# 13_FLOW_Sensor.net
KiCad netlist of a schematic drawn in Altium Designer
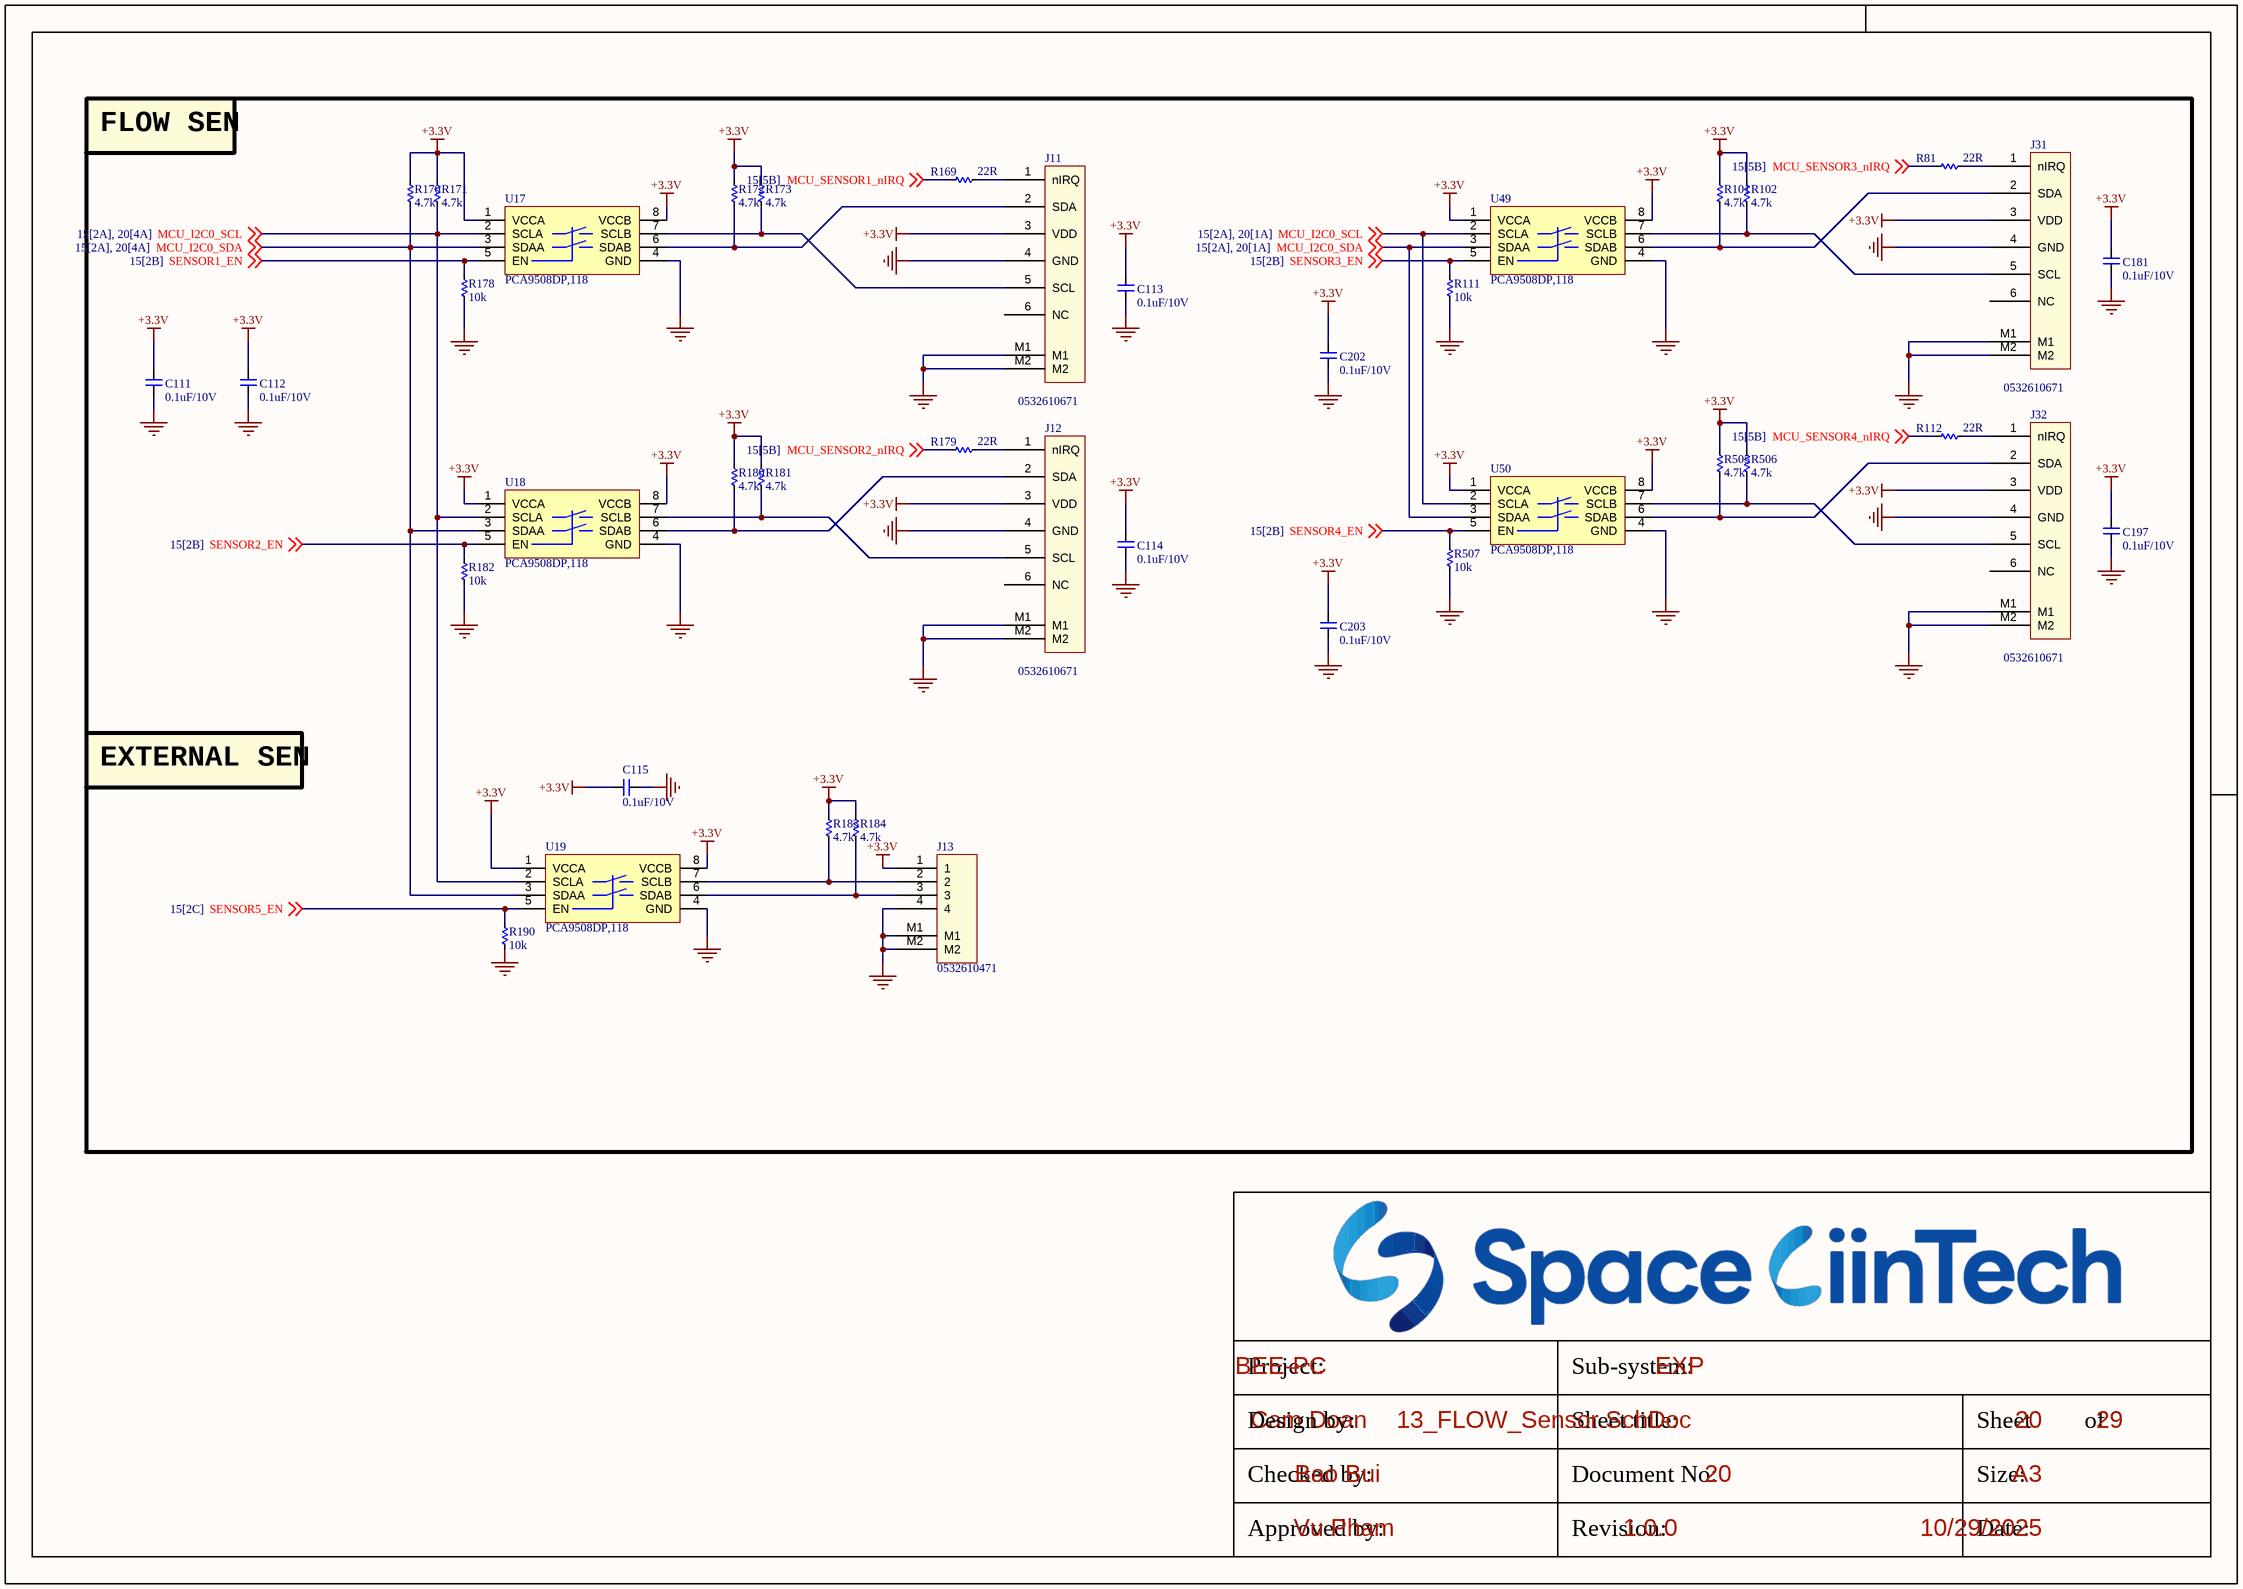
[diagram p0: 13_FLOW_Sensor.SchDoc]

(export (version "E")
  (design (tool "Eeschema 10.0.6"))
  (components
    (comp (ref "C111")
      (value "0.1uF/10V")
      (footprint "CAP_C_1005X60")
      (description "CAP CHIP")
      (libsource (lib "LABLIB") (part "_CAP_C_2"))
    )
    (comp (ref "C112")
      (value "0.1uF/10V")
      (footprint "CAP_C_1005X60")
      (description "CAP CHIP")
      (libsource (lib "LABLIB") (part "_CAP_C_2"))
    )
    (comp (ref "C113")
      (value "0.1uF/10V")
      (footprint "CAP_C_1005X60")
      (description "CAP CHIP")
      (libsource (lib "LABLIB") (part "_CAP_C_2"))
    )
    (comp (ref "C114")
      (value "0.1uF/10V")
      (footprint "CAP_C_1005X60")
      (description "CAP CHIP")
      (libsource (lib "LABLIB") (part "_CAP_C_2"))
    )
    (comp (ref "C115")
      (value "0.1uF/10V")
      (footprint "CAP_C_1005X60")
      (description "CAP CHIP")
      (libsource (lib "LABLIB") (part "_CAP_C_2"))
    )
    (comp (ref "C181")
      (value "0.1uF/10V")
      (footprint "CAP_C_1005X60")
      (description "CAP CHIP")
      (libsource (lib "LABLIB") (part "_CAP_C_2"))
    )
    (comp (ref "C197")
      (value "0.1uF/10V")
      (footprint "CAP_C_1005X60")
      (description "CAP CHIP")
      (libsource (lib "LABLIB") (part "_CAP_C_2"))
    )
    (comp (ref "C202")
      (value "0.1uF/10V")
      (footprint "CAP_C_1005X60")
      (description "CAP CHIP")
      (libsource (lib "LABLIB") (part "_CAP_C_2"))
    )
    (comp (ref "C203")
      (value "0.1uF/10V")
      (footprint "CAP_C_1005X60")
      (description "CAP CHIP")
      (libsource (lib "LABLIB") (part "_CAP_C_2"))
    )
    (comp (ref "J11")
      (value "0532610671")
      (footprint "MOLEX_0532610671")
      (libsource (lib "new_component") (part "FLOW_SENSOR"))
    )
    (comp (ref "J12")
      (value "0532610671")
      (footprint "MOLEX_0532610671")
      (libsource (lib "new_component") (part "FLOW_SENSOR"))
    )
    (comp (ref "J13")
      (value "0532610471")
      (footprint "MOLEX_0532610471")
      (libsource (lib "LABLIB") (part "Header 4x1_2M"))
    )
    (comp (ref "J31")
      (value "0532610671")
      (footprint "MOLEX_0532610671")
      (libsource (lib "new_component") (part "FLOW_SENSOR"))
    )
    (comp (ref "J32")
      (value "0532610671")
      (footprint "MOLEX_0532610671")
      (libsource (lib "new_component") (part "FLOW_SENSOR"))
    )
    (comp (ref "R81")
      (value "22R")
      (footprint "RES_C_1005X40")
      (description "RES")
      (libsource (lib "LABLIB") (part "_RES_B_2"))
    )
    (comp (ref "R101")
      (value "4.7k")
      (footprint "RES_C_1005X40")
      (description "RES")
      (libsource (lib "LABLIB") (part "_RES_B_2"))
    )
    (comp (ref "R102")
      (value "4.7k")
      (footprint "RES_C_1005X40")
      (description "RES")
      (libsource (lib "LABLIB") (part "_RES_B_2"))
    )
    (comp (ref "R111")
      (value "10k")
      (footprint "RES_C_1005X40")
      (description "RES")
      (libsource (lib "LABLIB") (part "_RES_B_2"))
    )
    (comp (ref "R112")
      (value "22R")
      (footprint "RES_C_1005X40")
      (description "RES")
      (libsource (lib "LABLIB") (part "_RES_B_2"))
    )
    (comp (ref "R169")
      (value "22R")
      (footprint "RES_C_1005X40")
      (description "RES")
      (libsource (lib "LABLIB") (part "_RES_B_2"))
    )
    (comp (ref "R170")
      (value "4.7k")
      (footprint "RES_C_1005X40")
      (description "RES")
      (libsource (lib "LABLIB") (part "_RES_B_2"))
    )
    (comp (ref "R171")
      (value "4.7k")
      (footprint "RES_C_1005X40")
      (description "RES")
      (libsource (lib "LABLIB") (part "_RES_B_2"))
    )
    (comp (ref "R172")
      (value "4.7k")
      (footprint "RES_C_1005X40")
      (description "RES")
      (libsource (lib "LABLIB") (part "_RES_B_2"))
    )
    (comp (ref "R173")
      (value "4.7k")
      (footprint "RES_C_1005X40")
      (description "RES")
      (libsource (lib "LABLIB") (part "_RES_B_2"))
    )
    (comp (ref "R178")
      (value "10k")
      (footprint "RES_C_1005X40")
      (description "RES")
      (libsource (lib "LABLIB") (part "_RES_B_2"))
    )
    (comp (ref "R179")
      (value "22R")
      (footprint "RES_C_1005X40")
      (description "RES")
      (libsource (lib "LABLIB") (part "_RES_B_2"))
    )
    (comp (ref "R180")
      (value "4.7k")
      (footprint "RES_C_1005X40")
      (description "RES")
      (libsource (lib "LABLIB") (part "_RES_B_2"))
    )
    (comp (ref "R181")
      (value "4.7k")
      (footprint "RES_C_1005X40")
      (description "RES")
      (libsource (lib "LABLIB") (part "_RES_B_2"))
    )
    (comp (ref "R182")
      (value "10k")
      (footprint "RES_C_1005X40")
      (description "RES")
      (libsource (lib "LABLIB") (part "_RES_B_2"))
    )
    (comp (ref "R183")
      (value "4.7k")
      (footprint "RES_C_1005X40")
      (description "RES")
      (libsource (lib "LABLIB") (part "_RES_B_2"))
    )
    (comp (ref "R184")
      (value "4.7k")
      (footprint "RES_C_1005X40")
      (description "RES")
      (libsource (lib "LABLIB") (part "_RES_B_2"))
    )
    (comp (ref "R190")
      (value "10k")
      (footprint "RES_C_1005X40")
      (description "RES")
      (libsource (lib "LABLIB") (part "_RES_B_2"))
    )
    (comp (ref "R505")
      (value "4.7k")
      (footprint "RES_C_1005X40")
      (description "RES")
      (libsource (lib "LABLIB") (part "_RES_B_2"))
    )
    (comp (ref "R506")
      (value "4.7k")
      (footprint "RES_C_1005X40")
      (description "RES")
      (libsource (lib "LABLIB") (part "_RES_B_2"))
    )
    (comp (ref "R507")
      (value "10k")
      (footprint "RES_C_1005X40")
      (description "RES")
      (libsource (lib "LABLIB") (part "_RES_B_2"))
    )
    (comp (ref "U17")
      (value "PCA9508DP,118")
      (footprint "TSOP8")
      (libsource (lib "EXP_HW_V3") (part "PCA9508DP,118"))
    )
    (comp (ref "U18")
      (value "PCA9508DP,118")
      (footprint "TSOP8")
      (libsource (lib "EXP_HW_V3") (part "PCA9508DP,118"))
    )
    (comp (ref "U19")
      (value "PCA9508DP,118")
      (footprint "TSOP8")
      (libsource (lib "EXP_HW_V3") (part "PCA9508DP,118"))
    )
    (comp (ref "U49")
      (value "PCA9508DP,118")
      (footprint "TSOP8")
      (libsource (lib "EXP_HW_V3") (part "PCA9508DP,118"))
    )
    (comp (ref "U50")
      (value "PCA9508DP,118")
      (footprint "TSOP8")
      (libsource (lib "EXP_HW_V3") (part "PCA9508DP,118"))
    )
  )
  (nets
    (net (code "1") (name "+3.3V") (class "Default")
      (node (ref "C111") (pin "2") (pinfunction "2_2") (pintype "passive"))
      (node (ref "C112") (pin "2") (pinfunction "2_2") (pintype "passive"))
      (node (ref "C113") (pin "2") (pinfunction "2_2") (pintype "passive"))
      (node (ref "C114") (pin "2") (pinfunction "2_2") (pintype "passive"))
      (node (ref "C115") (pin "2") (pinfunction "2_2") (pintype "passive"))
      (node (ref "C181") (pin "2") (pinfunction "2_2") (pintype "passive"))
      (node (ref "C197") (pin "2") (pinfunction "2_2") (pintype "passive"))
      (node (ref "C202") (pin "2") (pinfunction "2_2") (pintype "passive"))
      (node (ref "C203") (pin "2") (pinfunction "2_2") (pintype "passive"))
      (node (ref "J11") (pin "3") (pinfunction "VDD_3") (pintype "passive"))
      (node (ref "J12") (pin "3") (pinfunction "VDD_3") (pintype "passive"))
      (node (ref "J13") (pin "1") (pinfunction "1_1") (pintype "passive"))
      (node (ref "J31") (pin "3") (pinfunction "VDD_3") (pintype "passive"))
      (node (ref "J32") (pin "3") (pinfunction "VDD_3") (pintype "passive"))
      (node (ref "R101") (pin "1") (pinfunction "1_1") (pintype "passive"))
      (node (ref "R102") (pin "1") (pinfunction "1_1") (pintype "passive"))
      (node (ref "R170") (pin "1") (pinfunction "1_1") (pintype "passive"))
      (node (ref "R171") (pin "1") (pinfunction "1_1") (pintype "passive"))
      (node (ref "R172") (pin "1") (pinfunction "1_1") (pintype "passive"))
      (node (ref "R173") (pin "1") (pinfunction "1_1") (pintype "passive"))
      (node (ref "R180") (pin "1") (pinfunction "1_1") (pintype "passive"))
      (node (ref "R181") (pin "1") (pinfunction "1_1") (pintype "passive"))
      (node (ref "R183") (pin "1") (pinfunction "1_1") (pintype "passive"))
      (node (ref "R184") (pin "1") (pinfunction "1_1") (pintype "passive"))
      (node (ref "R505") (pin "1") (pinfunction "1_1") (pintype "passive"))
      (node (ref "R506") (pin "1") (pinfunction "1_1") (pintype "passive"))
      (node (ref "U17") (pin "1") (pinfunction "VCCA_1") (pintype "passive"))
      (node (ref "U17") (pin "8") (pinfunction "VCCB_8") (pintype "passive"))
      (node (ref "U18") (pin "1") (pinfunction "VCCA_1") (pintype "passive"))
      (node (ref "U18") (pin "8") (pinfunction "VCCB_8") (pintype "passive"))
      (node (ref "U19") (pin "1") (pinfunction "VCCA_1") (pintype "passive"))
      (node (ref "U19") (pin "8") (pinfunction "VCCB_8") (pintype "passive"))
      (node (ref "U49") (pin "1") (pinfunction "VCCA_1") (pintype "passive"))
      (node (ref "U49") (pin "8") (pinfunction "VCCB_8") (pintype "passive"))
      (node (ref "U50") (pin "1") (pinfunction "VCCA_1") (pintype "passive"))
      (node (ref "U50") (pin "8") (pinfunction "VCCB_8") (pintype "passive"))
    )
    (net (code "2") (name "GND") (class "Default")
      (node (ref "C111") (pin "1") (pinfunction "1_1") (pintype "passive"))
      (node (ref "C112") (pin "1") (pinfunction "1_1") (pintype "passive"))
      (node (ref "C113") (pin "1") (pinfunction "1_1") (pintype "passive"))
      (node (ref "C114") (pin "1") (pinfunction "1_1") (pintype "passive"))
      (node (ref "C115") (pin "1") (pinfunction "1_1") (pintype "passive"))
      (node (ref "C181") (pin "1") (pinfunction "1_1") (pintype "passive"))
      (node (ref "C197") (pin "1") (pinfunction "1_1") (pintype "passive"))
      (node (ref "C202") (pin "1") (pinfunction "1_1") (pintype "passive"))
      (node (ref "C203") (pin "1") (pinfunction "1_1") (pintype "passive"))
      (node (ref "J11") (pin "4") (pinfunction "GND_4") (pintype "passive"))
      (node (ref "J11") (pin "M1") (pinfunction "M1_M1") (pintype "passive"))
      (node (ref "J11") (pin "M2") (pinfunction "M2_M2") (pintype "passive"))
      (node (ref "J12") (pin "4") (pinfunction "GND_4") (pintype "passive"))
      (node (ref "J12") (pin "M1") (pinfunction "M1_M1") (pintype "passive"))
      (node (ref "J12") (pin "M2") (pinfunction "M2_M2") (pintype "passive"))
      (node (ref "J13") (pin "4") (pinfunction "4_4") (pintype "passive"))
      (node (ref "J13") (pin "M1") (pinfunction "M1_M1") (pintype "passive"))
      (node (ref "J13") (pin "M2") (pinfunction "M2_M2") (pintype "passive"))
      (node (ref "J31") (pin "4") (pinfunction "GND_4") (pintype "passive"))
      (node (ref "J31") (pin "M1") (pinfunction "M1_M1") (pintype "passive"))
      (node (ref "J31") (pin "M2") (pinfunction "M2_M2") (pintype "passive"))
      (node (ref "J32") (pin "4") (pinfunction "GND_4") (pintype "passive"))
      (node (ref "J32") (pin "M1") (pinfunction "M1_M1") (pintype "passive"))
      (node (ref "J32") (pin "M2") (pinfunction "M2_M2") (pintype "passive"))
      (node (ref "R111") (pin "2") (pinfunction "2_2") (pintype "passive"))
      (node (ref "R178") (pin "2") (pinfunction "2_2") (pintype "passive"))
      (node (ref "R182") (pin "2") (pinfunction "2_2") (pintype "passive"))
      (node (ref "R190") (pin "2") (pinfunction "2_2") (pintype "passive"))
      (node (ref "R507") (pin "2") (pinfunction "2_2") (pintype "passive"))
      (node (ref "U17") (pin "4") (pinfunction "GND_4") (pintype "passive"))
      (node (ref "U18") (pin "4") (pinfunction "GND_4") (pintype "passive"))
      (node (ref "U19") (pin "4") (pinfunction "GND_4") (pintype "passive"))
      (node (ref "U49") (pin "4") (pinfunction "GND_4") (pintype "passive"))
      (node (ref "U50") (pin "4") (pinfunction "GND_4") (pintype "passive"))
    )
    (net (code "3") (name "MCU_I2C0_SCL") (class "Default")
      (node (ref "R171") (pin "2") (pinfunction "2_2") (pintype "passive"))
      (node (ref "U17") (pin "2") (pinfunction "SCLA_2") (pintype "passive"))
      (node (ref "U18") (pin "2") (pinfunction "SCLA_2") (pintype "passive"))
      (node (ref "U19") (pin "2") (pinfunction "SCLA_2") (pintype "passive"))
      (node (ref "U49") (pin "2") (pinfunction "SCLA_2") (pintype "passive"))
      (node (ref "U50") (pin "2") (pinfunction "SCLA_2") (pintype "passive"))
    )
    (net (code "4") (name "MCU_I2C0_SDA") (class "Default")
      (node (ref "R170") (pin "2") (pinfunction "2_2") (pintype "passive"))
      (node (ref "U17") (pin "3") (pinfunction "SDAA_3") (pintype "passive"))
      (node (ref "U18") (pin "3") (pinfunction "SDAA_3") (pintype "passive"))
      (node (ref "U19") (pin "3") (pinfunction "SDAA_3") (pintype "passive"))
      (node (ref "U49") (pin "3") (pinfunction "SDAA_3") (pintype "passive"))
      (node (ref "U50") (pin "3") (pinfunction "SDAA_3") (pintype "passive"))
    )
    (net (code "5") (name "MCU_SENSOR1_nIRQ") (class "Default")
      (node (ref "R169") (pin "2") (pinfunction "2_2") (pintype "passive"))
    )
    (net (code "6") (name "MCU_SENSOR2_nIRQ") (class "Default")
      (node (ref "R179") (pin "2") (pinfunction "2_2") (pintype "passive"))
    )
    (net (code "7") (name "MCU_SENSOR3_nIRQ") (class "Default")
      (node (ref "R81") (pin "2") (pinfunction "2_2") (pintype "passive"))
    )
    (net (code "8") (name "MCU_SENSOR4_nIRQ") (class "Default")
      (node (ref "R112") (pin "2") (pinfunction "2_2") (pintype "passive"))
    )
    (net (code "9") (name "Net-(J11-SCL)") (class "Default")
      (node (ref "J11") (pin "5") (pinfunction "SCL_5") (pintype "passive"))
      (node (ref "R173") (pin "2") (pinfunction "2_2") (pintype "passive"))
      (node (ref "U17") (pin "7") (pinfunction "SCLB_7") (pintype "passive"))
    )
    (net (code "10") (name "Net-(J11-SDA)") (class "Default")
      (node (ref "J11") (pin "2") (pinfunction "SDA_2") (pintype "passive"))
      (node (ref "R172") (pin "2") (pinfunction "2_2") (pintype "passive"))
      (node (ref "U17") (pin "6") (pinfunction "SDAB_6") (pintype "passive"))
    )
    (net (code "11") (name "Net-(J11-nIRQ)") (class "Default")
      (node (ref "J11") (pin "1") (pinfunction "nIRQ_1") (pintype "passive"))
      (node (ref "R169") (pin "1") (pinfunction "1_1") (pintype "passive"))
    )
    (net (code "12") (name "Net-(J12-SCL)") (class "Default")
      (node (ref "J12") (pin "5") (pinfunction "SCL_5") (pintype "passive"))
      (node (ref "R181") (pin "2") (pinfunction "2_2") (pintype "passive"))
      (node (ref "U18") (pin "7") (pinfunction "SCLB_7") (pintype "passive"))
    )
    (net (code "13") (name "Net-(J12-SDA)") (class "Default")
      (node (ref "J12") (pin "2") (pinfunction "SDA_2") (pintype "passive"))
      (node (ref "R180") (pin "2") (pinfunction "2_2") (pintype "passive"))
      (node (ref "U18") (pin "6") (pinfunction "SDAB_6") (pintype "passive"))
    )
    (net (code "14") (name "Net-(J12-nIRQ)") (class "Default")
      (node (ref "J12") (pin "1") (pinfunction "nIRQ_1") (pintype "passive"))
      (node (ref "R179") (pin "1") (pinfunction "1_1") (pintype "passive"))
    )
    (net (code "15") (name "Net-(J31-SCL)") (class "Default")
      (node (ref "J31") (pin "5") (pinfunction "SCL_5") (pintype "passive"))
      (node (ref "R102") (pin "2") (pinfunction "2_2") (pintype "passive"))
      (node (ref "U49") (pin "7") (pinfunction "SCLB_7") (pintype "passive"))
    )
    (net (code "16") (name "Net-(J31-SDA)") (class "Default")
      (node (ref "J31") (pin "2") (pinfunction "SDA_2") (pintype "passive"))
      (node (ref "R101") (pin "2") (pinfunction "2_2") (pintype "passive"))
      (node (ref "U49") (pin "6") (pinfunction "SDAB_6") (pintype "passive"))
    )
    (net (code "17") (name "Net-(J31-nIRQ)") (class "Default")
      (node (ref "J31") (pin "1") (pinfunction "nIRQ_1") (pintype "passive"))
      (node (ref "R81") (pin "1") (pinfunction "1_1") (pintype "passive"))
    )
    (net (code "18") (name "Net-(J32-SCL)") (class "Default")
      (node (ref "J32") (pin "5") (pinfunction "SCL_5") (pintype "passive"))
      (node (ref "R506") (pin "2") (pinfunction "2_2") (pintype "passive"))
      (node (ref "U50") (pin "7") (pinfunction "SCLB_7") (pintype "passive"))
    )
    (net (code "19") (name "Net-(J32-SDA)") (class "Default")
      (node (ref "J32") (pin "2") (pinfunction "SDA_2") (pintype "passive"))
      (node (ref "R505") (pin "2") (pinfunction "2_2") (pintype "passive"))
      (node (ref "U50") (pin "6") (pinfunction "SDAB_6") (pintype "passive"))
    )
    (net (code "20") (name "Net-(J32-nIRQ)") (class "Default")
      (node (ref "J32") (pin "1") (pinfunction "nIRQ_1") (pintype "passive"))
      (node (ref "R112") (pin "1") (pinfunction "1_1") (pintype "passive"))
    )
    (net (code "21") (name "Net-(U19-SCLB)") (class "Default")
      (node (ref "J13") (pin "2") (pinfunction "2_2") (pintype "passive"))
      (node (ref "R183") (pin "2") (pinfunction "2_2") (pintype "passive"))
      (node (ref "U19") (pin "7") (pinfunction "SCLB_7") (pintype "passive"))
    )
    (net (code "22") (name "Net-(U19-SDAB)") (class "Default")
      (node (ref "J13") (pin "3") (pinfunction "3_3") (pintype "passive"))
      (node (ref "R184") (pin "2") (pinfunction "2_2") (pintype "passive"))
      (node (ref "U19") (pin "6") (pinfunction "SDAB_6") (pintype "passive"))
    )
    (net (code "23") (name "SENSOR1_EN") (class "Default")
      (node (ref "R178") (pin "1") (pinfunction "1_1") (pintype "passive"))
      (node (ref "U17") (pin "5") (pinfunction "EN_5") (pintype "passive"))
    )
    (net (code "24") (name "SENSOR2_EN") (class "Default")
      (node (ref "R182") (pin "1") (pinfunction "1_1") (pintype "passive"))
      (node (ref "U18") (pin "5") (pinfunction "EN_5") (pintype "passive"))
    )
    (net (code "25") (name "SENSOR3_EN") (class "Default")
      (node (ref "R111") (pin "1") (pinfunction "1_1") (pintype "passive"))
      (node (ref "U49") (pin "5") (pinfunction "EN_5") (pintype "passive"))
    )
    (net (code "26") (name "SENSOR4_EN") (class "Default")
      (node (ref "R507") (pin "1") (pinfunction "1_1") (pintype "passive"))
      (node (ref "U50") (pin "5") (pinfunction "EN_5") (pintype "passive"))
    )
    (net (code "27") (name "SENSOR5_EN") (class "Default")
      (node (ref "R190") (pin "1") (pinfunction "1_1") (pintype "passive"))
      (node (ref "U19") (pin "5") (pinfunction "EN_5") (pintype "passive"))
    )
    (net (code "28") (name "unconnected-(J11-NC-Pad6)") (class "Default")
      (node (ref "J11") (pin "6") (pinfunction "NC_6") (pintype "passive"))
    )
    (net (code "29") (name "unconnected-(J12-NC-Pad6)") (class "Default")
      (node (ref "J12") (pin "6") (pinfunction "NC_6") (pintype "passive"))
    )
    (net (code "30") (name "unconnected-(J31-NC-Pad6)") (class "Default")
      (node (ref "J31") (pin "6") (pinfunction "NC_6") (pintype "passive"))
    )
    (net (code "31") (name "unconnected-(J32-NC-Pad6)") (class "Default")
      (node (ref "J32") (pin "6") (pinfunction "NC_6") (pintype "passive"))
    )
  )
)
